# SCH_BL28-3005S_Bargraph_to_HT16K33_LED_d.net
KiCad netlist of a schematic drawn in EasyEDA
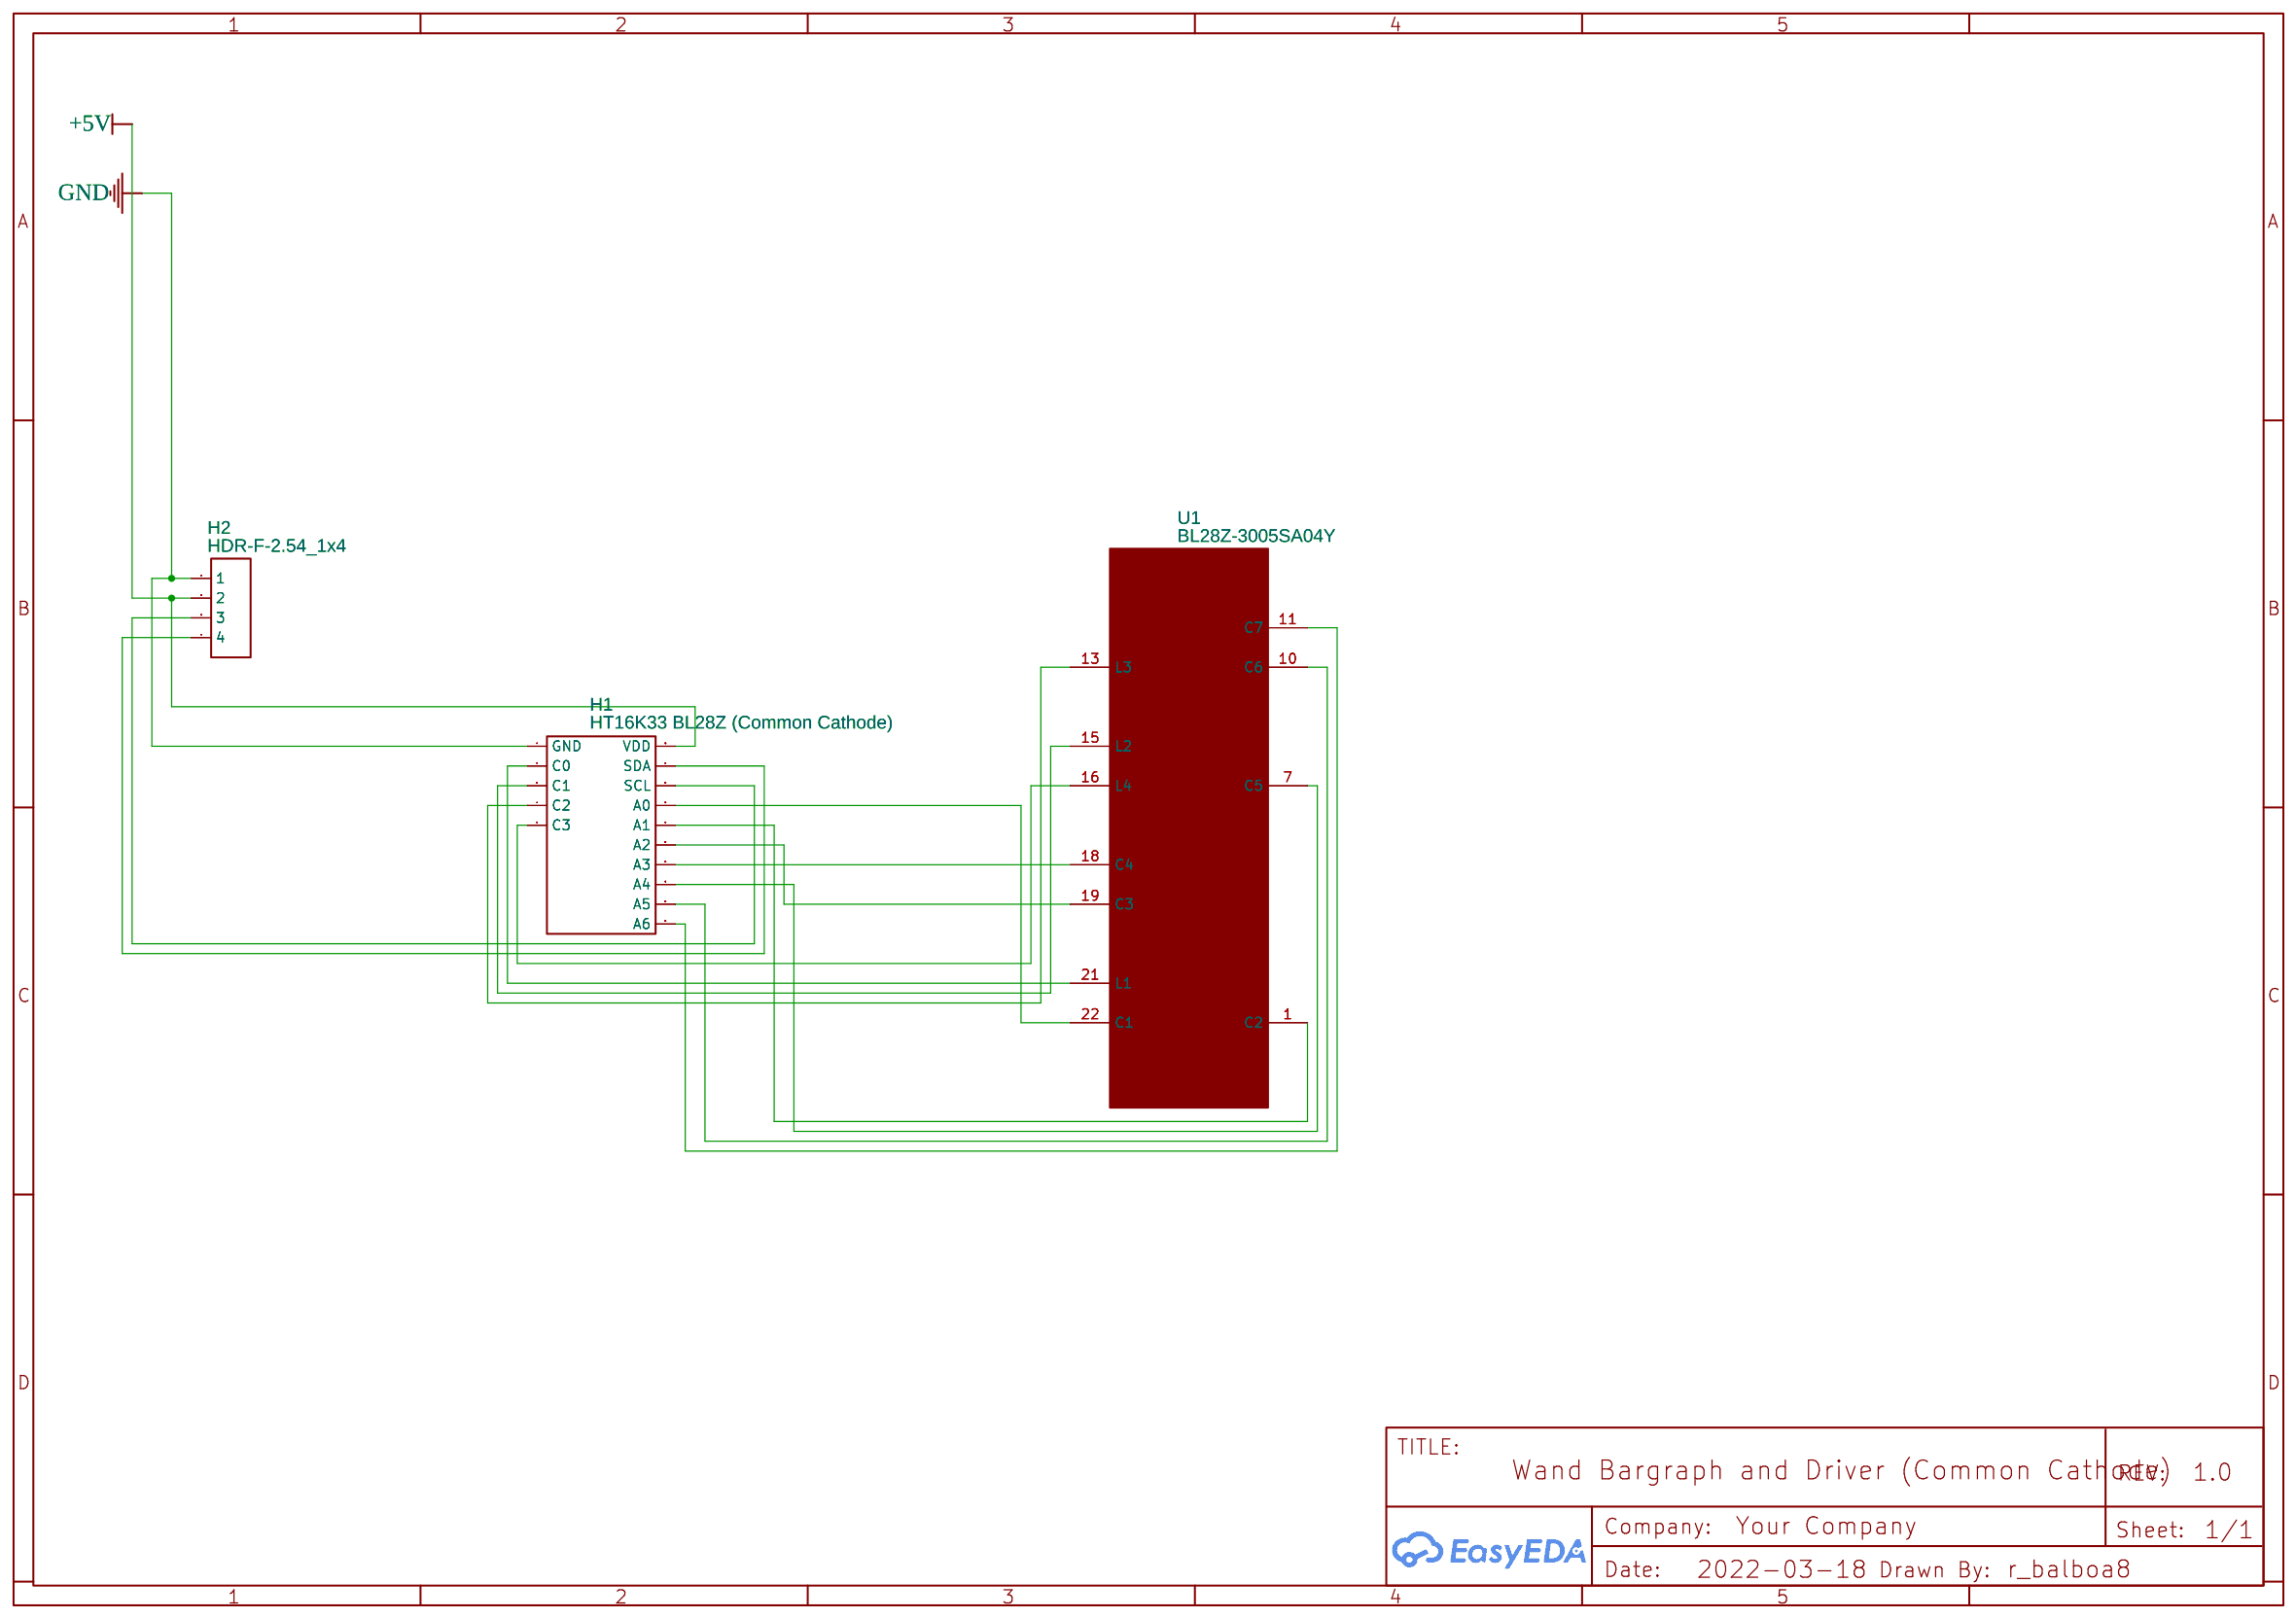
[diagram p0: schematic sheet]

(export (version "E")
  (design (tool "Eeschema 10.0.6"))
  (components
    (comp (ref "H1")
      (value "HT16K33 BL28Z (Common Cathode)")
      (fields (field (name "BOM_Supplier Part") "C225505"))
      (libsource (lib "") (part "HT16K33 BL28Z"))
    )
    (comp (ref "H2")
      (value "HDR-F-2.54_1x4")
      (fields (field (name "BOM_Supplier Part") "C225501"))
      (libsource (lib "") (part "HDR-F-2.54_1x4"))
    )
    (comp (ref "U1")
      (value "BL28Z-3005SA04Y")
      (fields (field (name "BOM_Manufacturer Part") "BL28-3005SDK04"))
      (libsource (lib "") (part "BL28Z-3005SA04Y"))
    )
  )
  (nets
    (net (code "1") (name "+5V") (class "Default")
      (node (ref "H1") (pin "28") (pinfunction "VDD_28") (pintype "unspecified"))
      (node (ref "H2") (pin "2") (pinfunction "2_2") (pintype "unspecified"))
    )
    (net (code "2") (name "GND") (class "Default")
      (node (ref "H1") (pin "1") (pinfunction "GND_1") (pintype "unspecified"))
      (node (ref "H2") (pin "1") (pinfunction "1_1") (pintype "unspecified"))
    )
    (net (code "3") (name "Net-(H1-A0)") (class "Default")
      (node (ref "H1") (pin "25") (pinfunction "A0_25") (pintype "unspecified"))
      (node (ref "U1") (pin "22") (pinfunction "C1_22") (pintype "unspecified"))
    )
    (net (code "4") (name "Net-(H1-A1)") (class "Default")
      (node (ref "H1") (pin "24") (pinfunction "A1_24") (pintype "unspecified"))
      (node (ref "U1") (pin "1") (pinfunction "C2_1") (pintype "unspecified"))
    )
    (net (code "5") (name "Net-(H1-A2)") (class "Default")
      (node (ref "H1") (pin "23") (pinfunction "A2_23") (pintype "unspecified"))
      (node (ref "U1") (pin "19") (pinfunction "C3_19") (pintype "unspecified"))
    )
    (net (code "6") (name "Net-(H1-A3)") (class "Default")
      (node (ref "H1") (pin "22") (pinfunction "A3_22") (pintype "unspecified"))
      (node (ref "U1") (pin "18") (pinfunction "C4_18") (pintype "unspecified"))
    )
    (net (code "7") (name "Net-(H1-A4)") (class "Default")
      (node (ref "H1") (pin "21") (pinfunction "A4_21") (pintype "unspecified"))
      (node (ref "U1") (pin "7") (pinfunction "C5_7") (pintype "unspecified"))
    )
    (net (code "8") (name "Net-(H1-A5)") (class "Default")
      (node (ref "H1") (pin "20") (pinfunction "A5_20") (pintype "unspecified"))
      (node (ref "U1") (pin "10") (pinfunction "C6_10") (pintype "unspecified"))
    )
    (net (code "9") (name "Net-(H1-A6)") (class "Default")
      (node (ref "H1") (pin "19") (pinfunction "A6_19") (pintype "unspecified"))
      (node (ref "U1") (pin "11") (pinfunction "C7_11") (pintype "unspecified"))
    )
    (net (code "10") (name "Net-(H1-C0)") (class "Default")
      (node (ref "H1") (pin "2") (pinfunction "C0_2") (pintype "unspecified"))
      (node (ref "U1") (pin "21") (pinfunction "L1_21") (pintype "unspecified"))
    )
    (net (code "11") (name "Net-(H1-C1)") (class "Default")
      (node (ref "H1") (pin "3") (pinfunction "C1_3") (pintype "unspecified"))
      (node (ref "U1") (pin "15") (pinfunction "L2_15") (pintype "unspecified"))
    )
    (net (code "12") (name "Net-(H1-C2)") (class "Default")
      (node (ref "H1") (pin "4") (pinfunction "C2_4") (pintype "unspecified"))
      (node (ref "U1") (pin "13") (pinfunction "L3_13") (pintype "unspecified"))
    )
    (net (code "13") (name "Net-(H1-C3)") (class "Default")
      (node (ref "H1") (pin "5") (pinfunction "C3_5") (pintype "unspecified"))
      (node (ref "U1") (pin "16") (pinfunction "L4_16") (pintype "unspecified"))
    )
    (net (code "14") (name "Net-(H1-SCL)") (class "Default")
      (node (ref "H1") (pin "26") (pinfunction "SCL_26") (pintype "unspecified"))
      (node (ref "H2") (pin "3") (pinfunction "3_3") (pintype "unspecified"))
    )
    (net (code "15") (name "Net-(H1-SDA)") (class "Default")
      (node (ref "H1") (pin "27") (pinfunction "SDA_27") (pintype "unspecified"))
      (node (ref "H2") (pin "4") (pinfunction "4_4") (pintype "unspecified"))
    )
  )
)
